# PowerCircuit.net
KiCad netlist of a schematic drawn in Altium Designer
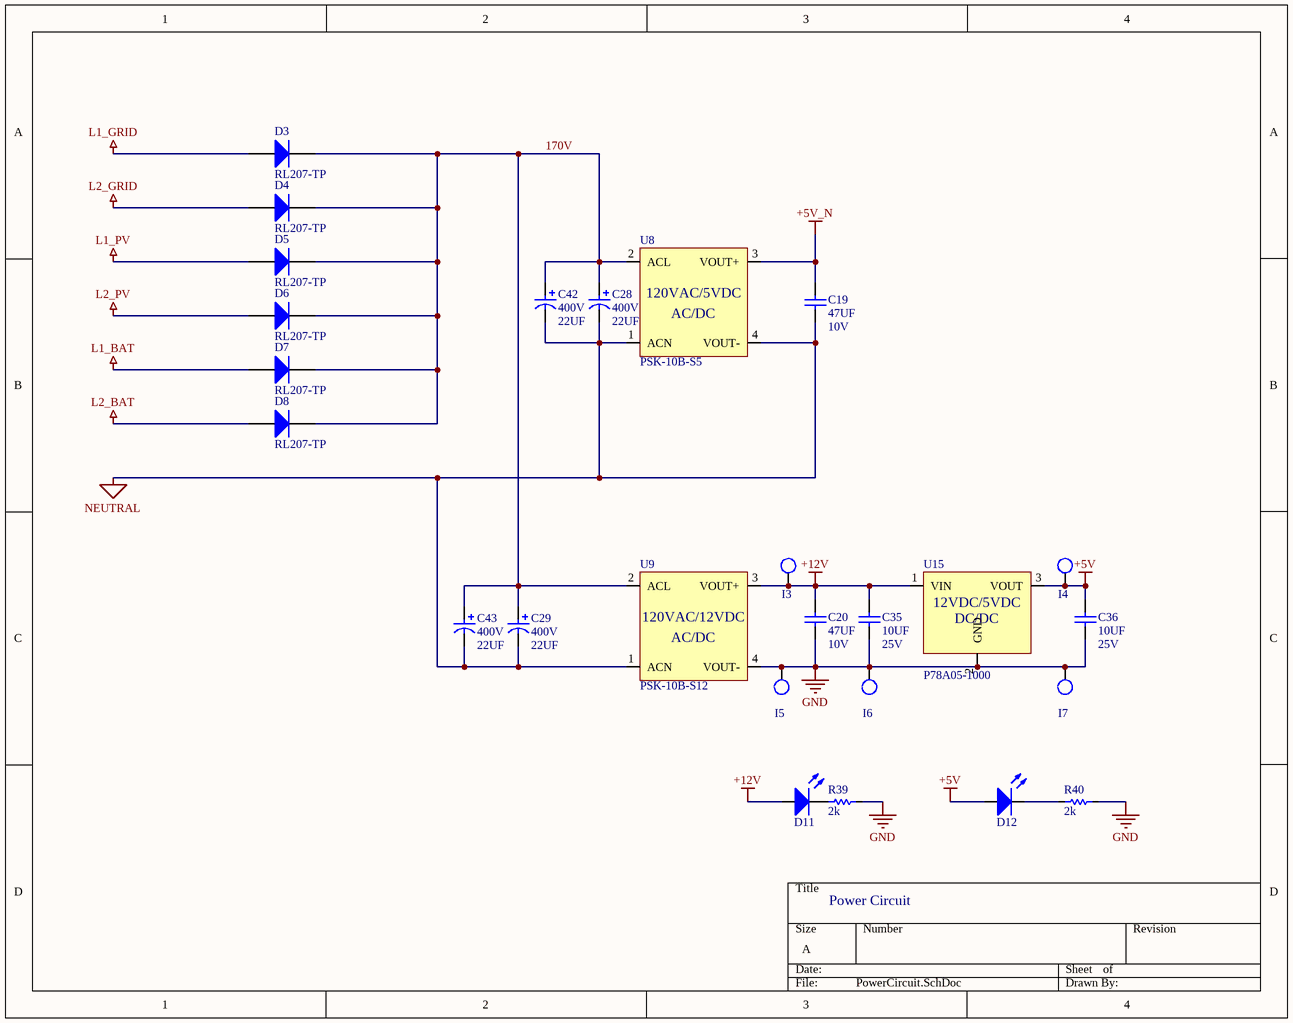
[diagram p0: PowerCircuit.SchDoc]

(export (version "E")
  (design (tool "Eeschema 10.0.6"))
  (components
    (comp (ref "C19")
      (value "GRM31CR61A476ME15L")
      (footprint "CAPC3216X16N")
      (description "CAP CER 47UF 10V X5R 1206")
      (fields
        (field (name "MANUFACTURER") "Murata Electronics North America")
        (field (name "CAPACITANCE") "47UF")
        (field (name "VOLTAGE - RATED") "10V")
      )
      (libsource (lib "IntelligentJunctionBox") (part "GRM31CR61A476ME15L"))
    )
    (comp (ref "C20")
      (value "GRM31CR61A476ME15L")
      (footprint "CAPC3216X16N")
      (description "CAP CER 47UF 10V X5R 1206")
      (fields
        (field (name "MANUFACTURER") "Murata Electronics North America")
        (field (name "CAPACITANCE") "47UF")
        (field (name "VOLTAGE - RATED") "10V")
      )
      (libsource (lib "IntelligentJunctionBox") (part "GRM31CR61A476ME15L"))
    )
    (comp (ref "C28")
      (value "22UF")
      (footprint "Radial-5mm")
      (description "CAP ALUM 22UF 20% 400V RADIAL")
      (fields
        (field (name "MANUFACTURER") "Nichicon")
        (field (name "MANUFACTURER PART NUMBER") "UCS2G220MHD")
        (field (name "VOLTAGE") "400V")
      )
      (libsource (lib "IntelligentJunctionBox") (part "UCS2G220MHD"))
    )
    (comp (ref "C29")
      (value "22UF")
      (footprint "Radial-5mm")
      (description "CAP ALUM 22UF 20% 400V RADIAL")
      (fields
        (field (name "MANUFACTURER") "Nichicon")
        (field (name "MANUFACTURER PART NUMBER") "UCS2G220MHD")
        (field (name "VOLTAGE") "400V")
      )
      (libsource (lib "IntelligentJunctionBox") (part "UCS2G220MHD"))
    )
    (comp (ref "C35")
      (value "GRM319R61E106KA12D")
      (footprint "CAPC3216X16N")
      (description "CAP CER 10UF 25V X5R 1206")
      (fields
        (field (name "MANUFACTURER") "Murata Electronics North America")
        (field (name "CAPACITANCE") "10UF")
        (field (name "VOLTAGE - RATED") "25V")
      )
      (libsource (lib "IntelligentJunctionBox") (part "GRM319R61E106KA12D"))
    )
    (comp (ref "C36")
      (value "GRM319R61E106KA12D")
      (footprint "CAPC3216X16N")
      (description "CAP CER 10UF 25V X5R 1206")
      (fields
        (field (name "MANUFACTURER") "Murata Electronics North America")
        (field (name "CAPACITANCE") "10UF")
        (field (name "VOLTAGE - RATED") "25V")
      )
      (libsource (lib "IntelligentJunctionBox") (part "GRM319R61E106KA12D"))
    )
    (comp (ref "C42")
      (value "22UF")
      (footprint "Radial-5mm")
      (description "CAP ALUM 22UF 20% 400V RADIAL")
      (fields
        (field (name "MANUFACTURER") "Nichicon")
        (field (name "MANUFACTURER PART NUMBER") "UCS2G220MHD")
        (field (name "VOLTAGE") "400V")
      )
      (libsource (lib "IntelligentJunctionBox") (part "UCS2G220MHD"))
    )
    (comp (ref "C43")
      (value "22UF")
      (footprint "Radial-5mm")
      (description "CAP ALUM 22UF 20% 400V RADIAL")
      (fields
        (field (name "MANUFACTURER") "Nichicon")
        (field (name "MANUFACTURER PART NUMBER") "UCS2G220MHD")
        (field (name "VOLTAGE") "400V")
      )
      (libsource (lib "IntelligentJunctionBox") (part "UCS2G220MHD"))
    )
    (comp (ref "D3")
      (value "RL207-TP")
      (footprint "DO-204AL")
      (description "DIODE GEN PURP 1KV 2A DO15")
      (fields (field (name "MANUFACTURER") "Micro Commercial Co."))
      (libsource (lib "IntelligentJunctionBox") (part "RL207-TP"))
    )
    (comp (ref "D4")
      (value "RL207-TP")
      (footprint "DO-204AL")
      (description "DIODE GEN PURP 1KV 2A DO15")
      (fields (field (name "MANUFACTURER") "Micro Commercial Co."))
      (libsource (lib "IntelligentJunctionBox") (part "RL207-TP"))
    )
    (comp (ref "D5")
      (value "RL207-TP")
      (footprint "DO-204AL")
      (description "DIODE GEN PURP 1KV 2A DO15")
      (fields (field (name "MANUFACTURER") "Micro Commercial Co."))
      (libsource (lib "IntelligentJunctionBox") (part "RL207-TP"))
    )
    (comp (ref "D6")
      (value "RL207-TP")
      (footprint "DO-204AL")
      (description "DIODE GEN PURP 1KV 2A DO15")
      (fields (field (name "MANUFACTURER") "Micro Commercial Co."))
      (libsource (lib "IntelligentJunctionBox") (part "RL207-TP"))
    )
    (comp (ref "D7")
      (value "RL207-TP")
      (footprint "DO-204AL")
      (description "DIODE GEN PURP 1KV 2A DO15")
      (fields (field (name "MANUFACTURER") "Micro Commercial Co."))
      (libsource (lib "IntelligentJunctionBox") (part "RL207-TP"))
    )
    (comp (ref "D8")
      (value "RL207-TP")
      (footprint "DO-204AL")
      (description "DIODE GEN PURP 1KV 2A DO15")
      (fields (field (name "MANUFACTURER") "Micro Commercial Co."))
      (libsource (lib "IntelligentJunctionBox") (part "RL207-TP"))
    )
    (comp (ref "D11")
      (value "LTST-C190KGKT")
      (footprint "0603 LED")
      (description "LED GREEN CLEAR 0603 SMD")
      (fields (field (name "MANUFACTURER") "Lite-On Inc."))
      (libsource (lib "IntelligentJunctionBox") (part "LTST-C190KGKT"))
    )
    (comp (ref "D12")
      (value "LTST-C190KGKT")
      (footprint "0603 LED")
      (description "LED GREEN CLEAR 0603 SMD")
      (fields (field (name "MANUFACTURER") "Lite-On Inc."))
      (libsource (lib "IntelligentJunctionBox") (part "LTST-C190KGKT"))
    )
    (comp (ref "I3")
      (value "Testpoint")
      (footprint "Testpoint")
      (libsource (lib "IntelligentJunctionBox") (part "Testpoint"))
    )
    (comp (ref "I4")
      (value "Testpoint")
      (footprint "Testpoint")
      (libsource (lib "IntelligentJunctionBox") (part "Testpoint"))
    )
    (comp (ref "I5")
      (value "Testpoint")
      (footprint "Testpoint")
      (libsource (lib "IntelligentJunctionBox") (part "Testpoint"))
    )
    (comp (ref "I6")
      (value "Testpoint")
      (footprint "Testpoint")
      (libsource (lib "IntelligentJunctionBox") (part "Testpoint"))
    )
    (comp (ref "I7")
      (value "Testpoint")
      (footprint "Testpoint")
      (libsource (lib "IntelligentJunctionBox") (part "Testpoint"))
    )
    (comp (ref "R39")
      (value "RC0603FR-072KL")
      (footprint "RESC1608X06N")
      (description "RES SMD 2K OHM 1% 1/10W 0603")
      (fields (field (name "MANUFACTURER") "Yageo") (field (name "RESISTANCE") "2k"))
      (libsource (lib "IntelligentJunctionBox") (part "RC0603FR-072KL"))
    )
    (comp (ref "R40")
      (value "RC0603FR-072KL")
      (footprint "RESC1608X06N")
      (description "RES SMD 2K OHM 1% 1/10W 0603")
      (fields (field (name "MANUFACTURER") "Yageo") (field (name "RESISTANCE") "2k"))
      (libsource (lib "IntelligentJunctionBox") (part "RC0603FR-072KL"))
    )
    (comp (ref "U8")
      (value "PSK-10B-S5")
      (footprint "PSK-10B-S5")
      (description "AC/DC CONVERTER 120V-5V 10W")
      (fields (field (name "MANUFACTURER") "CUI Inc."))
      (libsource (lib "IntelligentJunctionBox") (part "PSK-10B-S5"))
    )
    (comp (ref "U9")
      (value "PSK-10B-S12")
      (footprint "PSK-10B-S5")
      (description "AC/DC CONVERTER 120V-12V 10W")
      (fields (field (name "MANUFACTURER") "CUI Inc."))
      (libsource (lib "IntelligentJunctionBox") (part "PSK-10B-S12"))
    )
    (comp (ref "U15")
      (value "P78A05-1000")
      (footprint "P78A05-1000")
      (description "DC/DC CONVERTER 5V 5W")
      (fields (field (name "MANUFACTURER") "CUI Inc."))
      (libsource (lib "IntelligentJunctionBox") (part "P78A05-1000"))
    )
  )
  (nets
    (net (code "1") (name "+5V") (class "Default")
      (node (ref "C36") (pin "2") (pinfunction "2_2") (pintype "passive"))
      (node (ref "D12") (pin "1") (pinfunction "A_1") (pintype "passive"))
      (node (ref "I4") (pin "1") (pinfunction "TP_1") (pintype "passive"))
      (node (ref "U15") (pin "3") (pinfunction "VOUT_3") (pintype "passive"))
    )
    (net (code "2") (name "+5V_N") (class "Default")
      (node (ref "C19") (pin "2") (pinfunction "2_2") (pintype "passive"))
      (node (ref "U8") (pin "3") (pinfunction "VOUT+_3") (pintype "passive"))
    )
    (net (code "3") (name "+12V") (class "Default")
      (node (ref "C20") (pin "2") (pinfunction "2_2") (pintype "passive"))
      (node (ref "C35") (pin "2") (pinfunction "2_2") (pintype "passive"))
      (node (ref "D11") (pin "1") (pinfunction "A_1") (pintype "passive"))
      (node (ref "I3") (pin "1") (pinfunction "TP_1") (pintype "passive"))
      (node (ref "U15") (pin "1") (pinfunction "VIN_1") (pintype "passive"))
      (node (ref "U9") (pin "3") (pinfunction "VOUT+_3") (pintype "passive"))
    )
    (net (code "4") (name "/170V") (class "Default")
      (node (ref "C28") (pin "1") (pinfunction "1_1") (pintype "passive"))
      (node (ref "C29") (pin "1") (pinfunction "1_1") (pintype "passive"))
      (node (ref "C42") (pin "1") (pinfunction "1_1") (pintype "passive"))
      (node (ref "C43") (pin "1") (pinfunction "1_1") (pintype "passive"))
      (node (ref "D3") (pin "2") (pinfunction "K_2") (pintype "passive"))
      (node (ref "D4") (pin "2") (pinfunction "K_2") (pintype "passive"))
      (node (ref "D5") (pin "2") (pinfunction "K_2") (pintype "passive"))
      (node (ref "D6") (pin "2") (pinfunction "K_2") (pintype "passive"))
      (node (ref "D7") (pin "2") (pinfunction "K_2") (pintype "passive"))
      (node (ref "D8") (pin "2") (pinfunction "K_2") (pintype "passive"))
      (node (ref "U8") (pin "2") (pinfunction "ACL_2") (pintype "passive"))
      (node (ref "U9") (pin "2") (pinfunction "ACL_2") (pintype "passive"))
    )
    (net (code "5") (name "GND") (class "Default")
      (node (ref "C20") (pin "1") (pinfunction "1_1") (pintype "passive"))
      (node (ref "C35") (pin "1") (pinfunction "1_1") (pintype "passive"))
      (node (ref "C36") (pin "1") (pinfunction "1_1") (pintype "passive"))
      (node (ref "I5") (pin "1") (pinfunction "TP_1") (pintype "passive"))
      (node (ref "I6") (pin "1") (pinfunction "TP_1") (pintype "passive"))
      (node (ref "I7") (pin "1") (pinfunction "TP_1") (pintype "passive"))
      (node (ref "R39") (pin "2") (pinfunction "2_2") (pintype "passive"))
      (node (ref "R40") (pin "2") (pinfunction "2_2") (pintype "passive"))
      (node (ref "U15") (pin "2") (pinfunction "GND_2") (pintype "passive"))
      (node (ref "U9") (pin "4") (pinfunction "VOUT-_4") (pintype "passive"))
    )
    (net (code "6") (name "L1_BAT") (class "Default")
      (node (ref "D7") (pin "1") (pinfunction "A_1") (pintype "passive"))
    )
    (net (code "7") (name "L1_GRID") (class "Default")
      (node (ref "D3") (pin "1") (pinfunction "A_1") (pintype "passive"))
    )
    (net (code "8") (name "L1_PV") (class "Default")
      (node (ref "D5") (pin "1") (pinfunction "A_1") (pintype "passive"))
    )
    (net (code "9") (name "L2_BAT") (class "Default")
      (node (ref "D8") (pin "1") (pinfunction "A_1") (pintype "passive"))
    )
    (net (code "10") (name "L2_GRID") (class "Default")
      (node (ref "D4") (pin "1") (pinfunction "A_1") (pintype "passive"))
    )
    (net (code "11") (name "L2_PV") (class "Default")
      (node (ref "D6") (pin "1") (pinfunction "A_1") (pintype "passive"))
    )
    (net (code "12") (name "NEUTRAL") (class "Default")
      (node (ref "C19") (pin "1") (pinfunction "1_1") (pintype "passive"))
      (node (ref "C28") (pin "2") (pinfunction "2_2") (pintype "passive"))
      (node (ref "C29") (pin "2") (pinfunction "2_2") (pintype "passive"))
      (node (ref "C42") (pin "2") (pinfunction "2_2") (pintype "passive"))
      (node (ref "C43") (pin "2") (pinfunction "2_2") (pintype "passive"))
      (node (ref "U8") (pin "1") (pinfunction "ACN_1") (pintype "passive"))
      (node (ref "U8") (pin "4") (pinfunction "VOUT-_4") (pintype "passive"))
      (node (ref "U9") (pin "1") (pinfunction "ACN_1") (pintype "passive"))
    )
    (net (code "13") (name "Net-(D11-K)") (class "Default")
      (node (ref "D11") (pin "2") (pinfunction "K_2") (pintype "passive"))
      (node (ref "R39") (pin "1") (pinfunction "1_1") (pintype "passive"))
    )
    (net (code "14") (name "Net-(D12-K)") (class "Default")
      (node (ref "D12") (pin "2") (pinfunction "K_2") (pintype "passive"))
      (node (ref "R40") (pin "1") (pinfunction "1_1") (pintype "passive"))
    )
  )
)
